# transducer_kVer.net
KiCad netlist of a schematic drawn in EAGLE
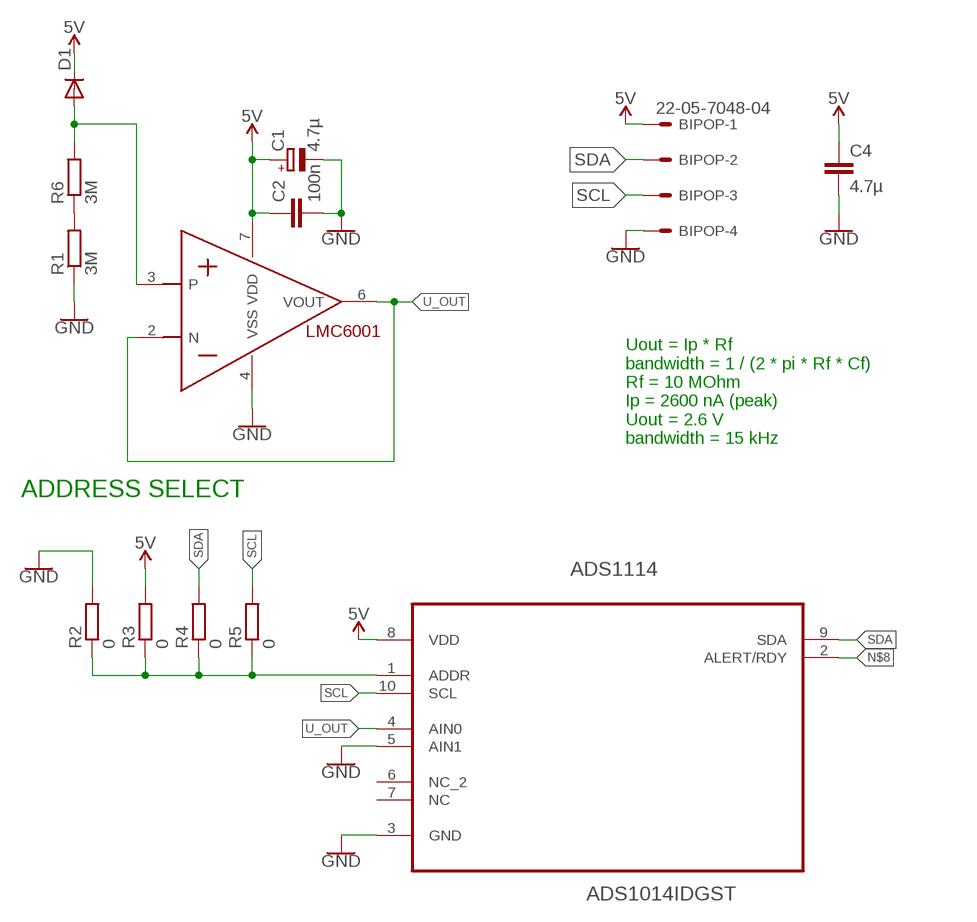
[diagram p0: schematic, sheet 1]

(export (version "E")
  (design (tool "Eeschema 10.0.6"))
  (components
    (comp (ref "ADS1114")
      (value "ADS1014IDGST")
      (footprint "eagle-import:SOP50P490X110-10N")
      (libsource (lib "eagle-import") (part "ADS1014IDGST"))
    )
    (comp (ref "BIPOP")
      (value "22-05-7048-04")
      (footprint "eagle-import:7395-04")
      (libsource (lib "eagle-import") (part "22-?-0405-7048"))
    )
    (comp (ref "C1")
      (value "4.7µ")
      (footprint "eagle-import:A_3216-18R")
      (libsource (lib "eagle-import") (part "CPOL-EUA/3216-18R"))
    )
    (comp (ref "C2")
      (value "100n")
      (footprint "eagle-import:C0805")
      (libsource (lib "eagle-import") (part "resistor_348_C-EUC0805"))
    )
    (comp (ref "C4")
      (value "4.7µ")
      (footprint "eagle-import:C0805")
      (libsource (lib "eagle-import") (part "C-EUC0805"))
    )
    (comp (ref "D1")
      (value "DIODE-TO18D")
      (footprint "eagle-import:TO18D")
      (libsource (lib "eagle-import") (part "DIODE-TO18D"))
    )
    (comp (ref "LMC6001")
      (value "LMC6001")
      (footprint "eagle-import:DIL08")
      (libsource (lib "eagle-import") (part "LMC6001"))
    )
    (comp (ref "R1")
      (value "3M")
      (footprint "eagle-import:R0805")
      (libsource (lib "eagle-import") (part "R-EU_R0805"))
    )
    (comp (ref "R2")
      (value "0")
      (footprint "eagle-import:R0805")
      (libsource (lib "eagle-import") (part "R-EU_R0805"))
    )
    (comp (ref "R3")
      (value "0")
      (footprint "eagle-import:R0805")
      (libsource (lib "eagle-import") (part "R-EU_R0805"))
    )
    (comp (ref "R4")
      (value "0")
      (footprint "eagle-import:R0805")
      (libsource (lib "eagle-import") (part "R-EU_R0805"))
    )
    (comp (ref "R5")
      (value "0")
      (footprint "eagle-import:R0805")
      (libsource (lib "eagle-import") (part "R-EU_R0805"))
    )
    (comp (ref "R6")
      (value "3M")
      (footprint "eagle-import:R0805")
      (libsource (lib "eagle-import") (part "R-EU_R0805"))
    )
  )
  (nets
    (net (code "1") (name "5V") (class "Default")
      (node (ref "ADS1114") (pin "8") (pinfunction "VDD_8") (pintype "power_in"))
      (node (ref "BIPOP") (pin "1") (pinfunction "S_1") (pintype "passive"))
      (node (ref "C1") (pin "+") (pinfunction "+_+") (pintype "passive"))
      (node (ref "C2") (pin "1") (pinfunction "1_1") (pintype "passive"))
      (node (ref "C4") (pin "1") (pinfunction "1_1") (pintype "passive"))
      (node (ref "D1") (pin "C") (pinfunction "C_C") (pintype "passive"))
      (node (ref "LMC6001") (pin "7") (pinfunction "VDD_7") (pintype "power_in"))
      (node (ref "R3") (pin "2") (pinfunction "2_2") (pintype "passive"))
    )
    (net (code "2") (name "GND") (class "Default")
      (node (ref "ADS1114") (pin "3") (pinfunction "GND_3") (pintype "passive"))
      (node (ref "ADS1114") (pin "5") (pinfunction "AIN1_5") (pintype "input"))
      (node (ref "BIPOP") (pin "4") (pinfunction "S_4") (pintype "passive"))
      (node (ref "C1") (pin "-") (pinfunction "-_-") (pintype "passive"))
      (node (ref "C2") (pin "2") (pinfunction "2_2") (pintype "passive"))
      (node (ref "C4") (pin "2") (pinfunction "2_2") (pintype "passive"))
      (node (ref "LMC6001") (pin "4") (pinfunction "VSS_4") (pintype "power_in"))
      (node (ref "R1") (pin "1") (pinfunction "1_1") (pintype "passive"))
      (node (ref "R2") (pin "2") (pinfunction "2_2") (pintype "passive"))
    )
    (net (code "3") (name "N$8") (class "Default")
      (node (ref "ADS1114") (pin "2") (pinfunction "ALERT/RDY_2") (pintype "output"))
    )
    (net (code "4") (name "Net-(ADS1114-ADDR)") (class "Default")
      (node (ref "ADS1114") (pin "1") (pinfunction "ADDR_1") (pintype "input"))
      (node (ref "R2") (pin "1") (pinfunction "1_1") (pintype "passive"))
      (node (ref "R3") (pin "1") (pinfunction "1_1") (pintype "passive"))
      (node (ref "R4") (pin "1") (pinfunction "1_1") (pintype "passive"))
      (node (ref "R5") (pin "1") (pinfunction "1_1") (pintype "passive"))
    )
    (net (code "5") (name "Net-(LMC6001-P)") (class "Default")
      (node (ref "D1") (pin "A") (pinfunction "A_A") (pintype "passive"))
      (node (ref "LMC6001") (pin "3") (pinfunction "P_3") (pintype "bidirectional"))
      (node (ref "R6") (pin "2") (pinfunction "2_2") (pintype "passive"))
    )
    (net (code "6") (name "Net-(R1-Pad2)") (class "Default")
      (node (ref "R1") (pin "2") (pinfunction "2_2") (pintype "passive"))
      (node (ref "R6") (pin "1") (pinfunction "1_1") (pintype "passive"))
    )
    (net (code "7") (name "SCL") (class "Default")
      (node (ref "ADS1114") (pin "10") (pinfunction "SCL_10") (pintype "input"))
      (node (ref "BIPOP") (pin "3") (pinfunction "S_3") (pintype "passive"))
      (node (ref "R5") (pin "2") (pinfunction "2_2") (pintype "passive"))
    )
    (net (code "8") (name "SDA") (class "Default")
      (node (ref "ADS1114") (pin "9") (pinfunction "SDA_9") (pintype "bidirectional"))
      (node (ref "BIPOP") (pin "2") (pinfunction "S_2") (pintype "passive"))
      (node (ref "R4") (pin "2") (pinfunction "2_2") (pintype "passive"))
    )
    (net (code "9") (name "U_OUT") (class "Default")
      (node (ref "ADS1114") (pin "4") (pinfunction "AIN0_4") (pintype "input"))
      (node (ref "LMC6001") (pin "2") (pinfunction "N_2") (pintype "bidirectional"))
      (node (ref "LMC6001") (pin "6") (pinfunction "VOUT_6") (pintype "bidirectional"))
    )
    (net (code "10") (name "unconnected-(ADS1114-NC-Pad7)") (class "Default")
      (node (ref "ADS1114") (pin "7") (pinfunction "NC_7") (pintype "no_connect"))
    )
    (net (code "11") (name "unconnected-(ADS1114-NC_2-Pad6)") (class "Default")
      (node (ref "ADS1114") (pin "6") (pinfunction "NC_2_6") (pintype "no_connect"))
    )
  )
)
